# Manipulator_loads.net
KiCad netlist of a schematic drawn in EAGLE
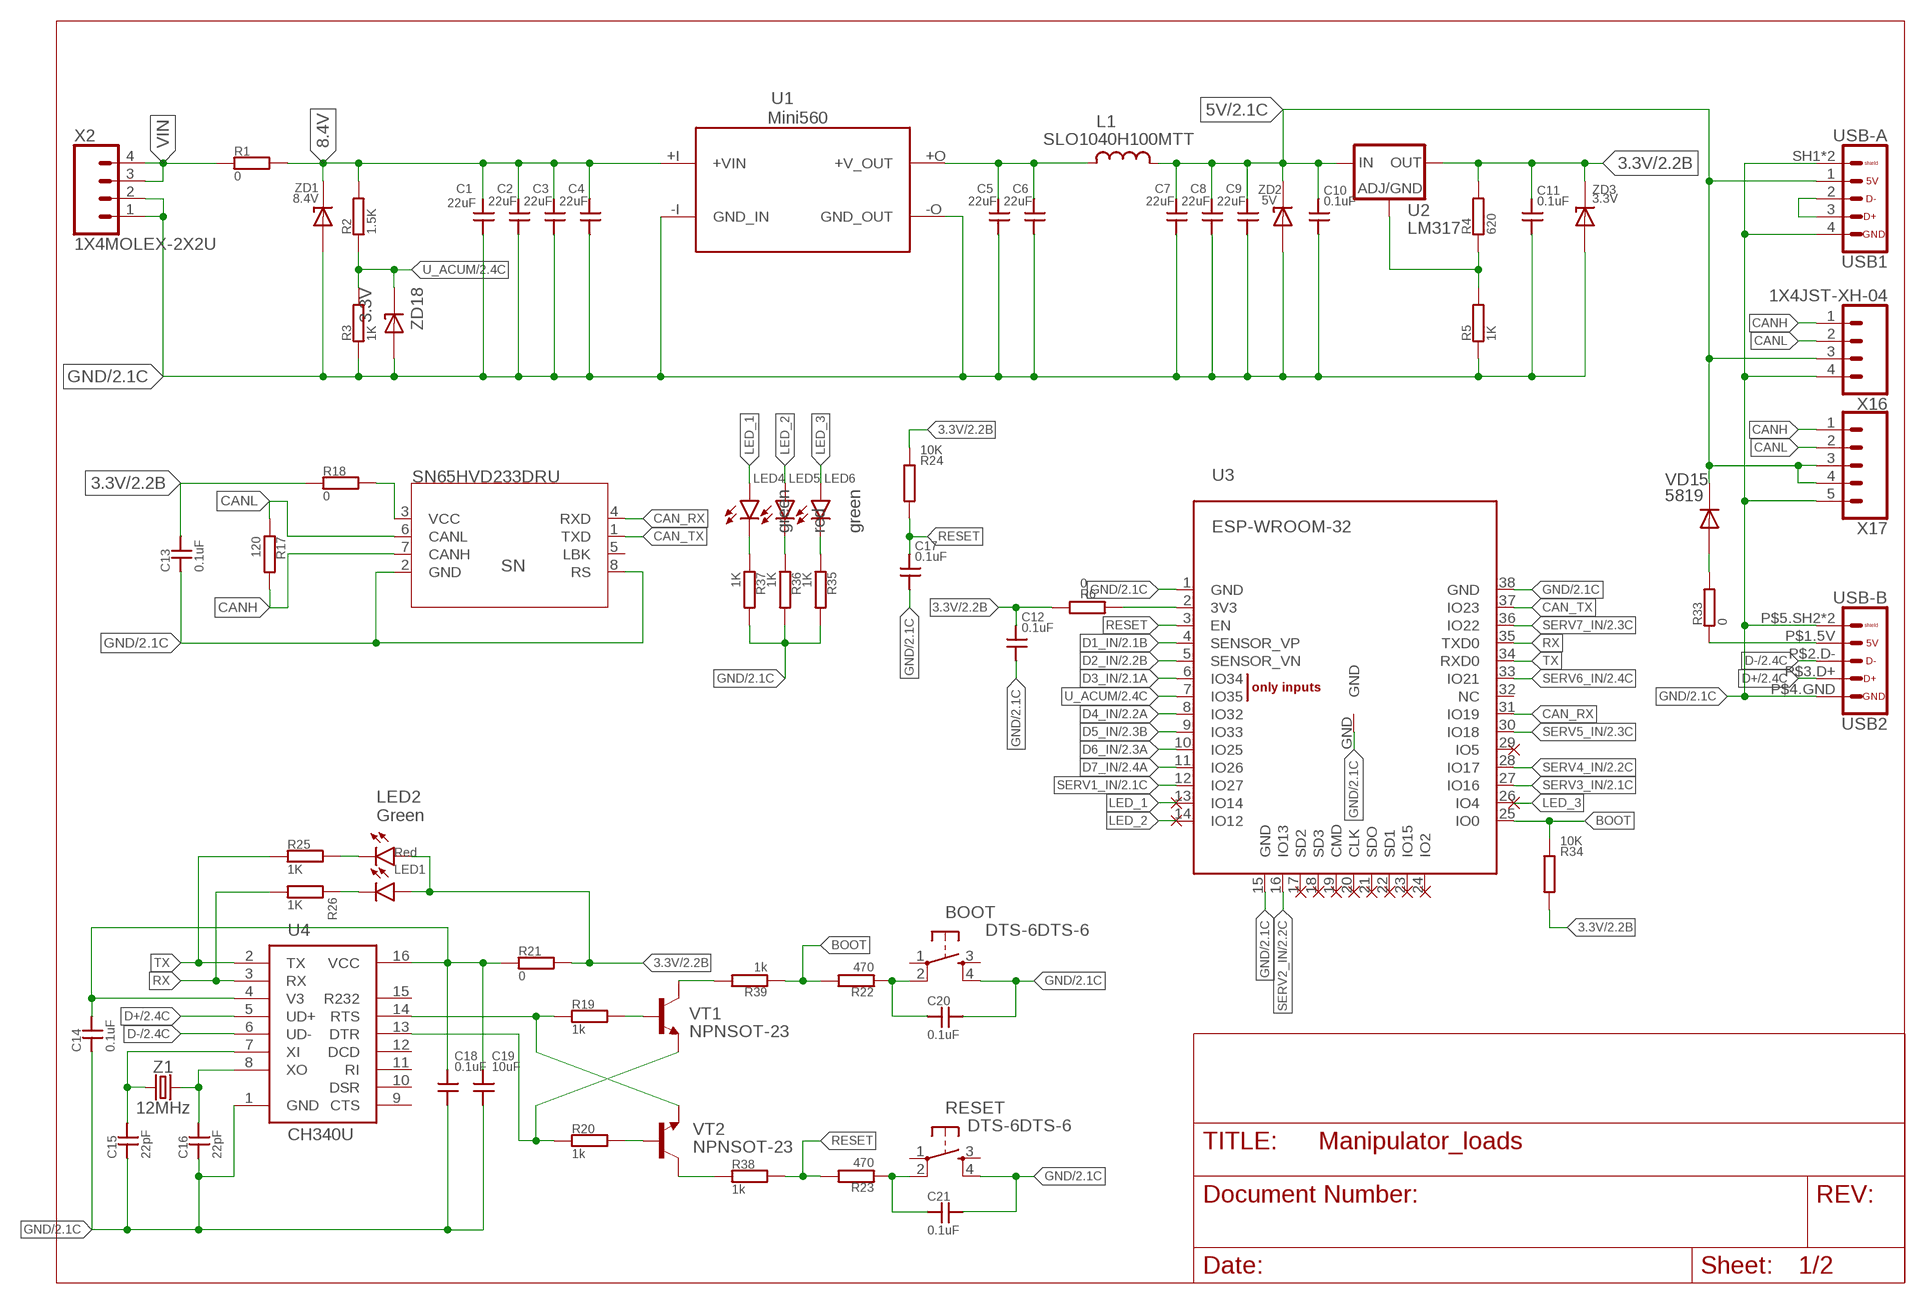
[diagram p0: schematic, sheet 1]
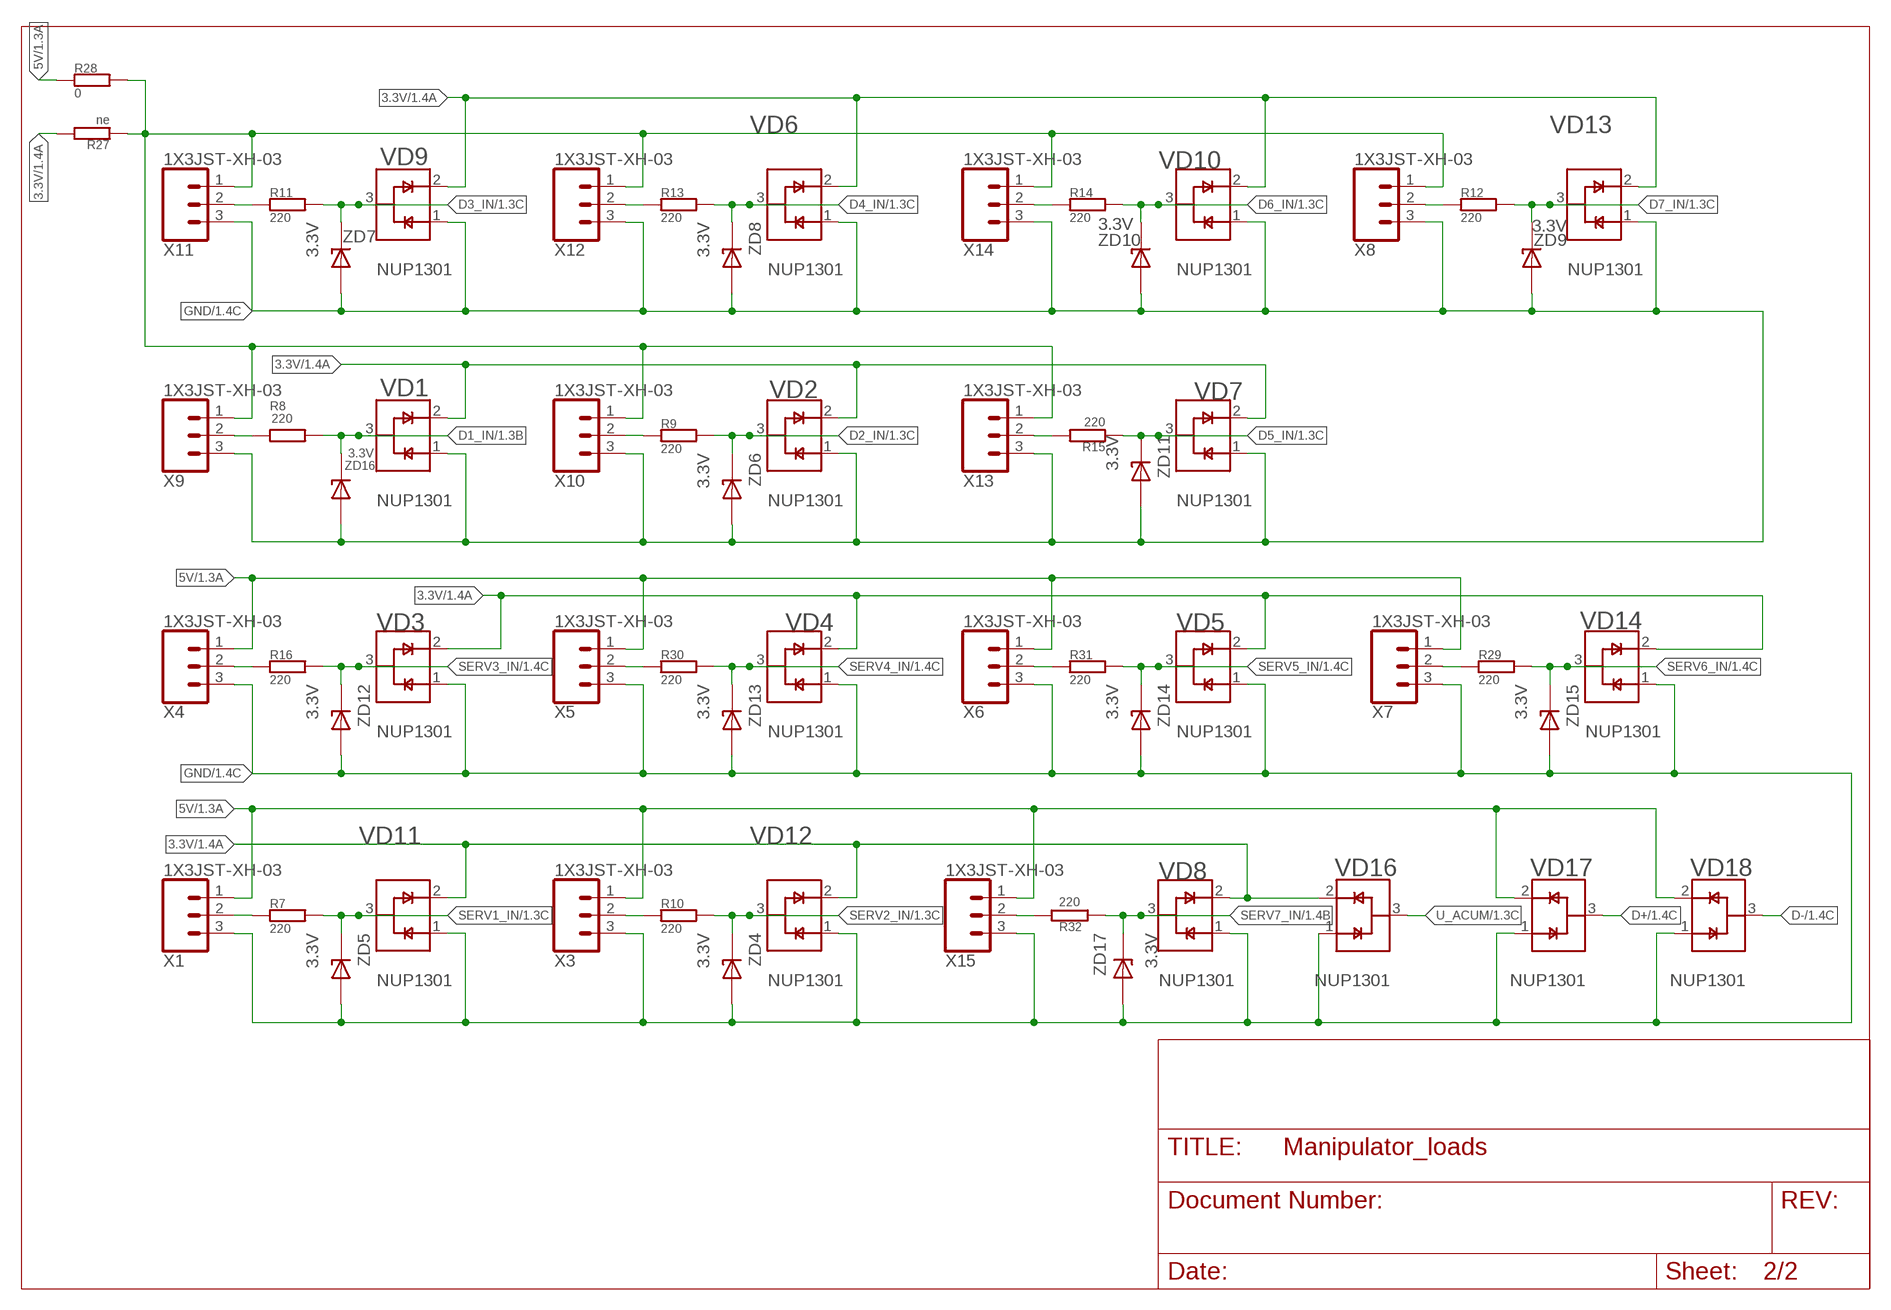
[diagram p1: schematic, sheet 2]

(export (version "E")
  (design (tool "Eeschema 10.0.6"))
  (components
    (comp (ref "BOOT")
      (value "DTS-6DTS-6")
      (footprint "eagle-import:DTS-6")
      (libsource (lib "eagle-import") (part "DTS-6DTS-6"))
    )
    (comp (ref "C1")
      (value "22uF")
      (footprint "eagle-import:1206")
      (libsource (lib "eagle-import") (part "C1206"))
    )
    (comp (ref "C2")
      (value "22uF")
      (footprint "eagle-import:1206")
      (libsource (lib "eagle-import") (part "C1206"))
    )
    (comp (ref "C3")
      (value "22uF")
      (footprint "eagle-import:1206")
      (libsource (lib "eagle-import") (part "C1206"))
    )
    (comp (ref "C4")
      (value "22uF")
      (footprint "eagle-import:1206")
      (libsource (lib "eagle-import") (part "C1206"))
    )
    (comp (ref "C5")
      (value "22uF")
      (footprint "eagle-import:1206")
      (libsource (lib "eagle-import") (part "C1206"))
    )
    (comp (ref "C6")
      (value "22uF")
      (footprint "eagle-import:1206")
      (libsource (lib "eagle-import") (part "C1206"))
    )
    (comp (ref "C7")
      (value "22uF")
      (footprint "eagle-import:1206")
      (libsource (lib "eagle-import") (part "C1206"))
    )
    (comp (ref "C8")
      (value "22uF")
      (footprint "eagle-import:1206")
      (libsource (lib "eagle-import") (part "C1206"))
    )
    (comp (ref "C9")
      (value "22uF")
      (footprint "eagle-import:1206")
      (libsource (lib "eagle-import") (part "C1206"))
    )
    (comp (ref "C10")
      (value "0.1uF")
      (footprint "eagle-import:0603")
      (libsource (lib "eagle-import") (part "C0603"))
    )
    (comp (ref "C11")
      (value "0.1uF")
      (footprint "eagle-import:0603")
      (libsource (lib "eagle-import") (part "C0603"))
    )
    (comp (ref "C12")
      (value "0.1uF")
      (footprint "eagle-import:0603")
      (libsource (lib "eagle-import") (part "C0603"))
    )
    (comp (ref "C13")
      (value "0.1uF")
      (footprint "eagle-import:0603")
      (libsource (lib "eagle-import") (part "C0603"))
    )
    (comp (ref "C14")
      (value "0.1uF")
      (footprint "eagle-import:0603")
      (libsource (lib "eagle-import") (part "C0603"))
    )
    (comp (ref "C15")
      (value "22pF")
      (footprint "eagle-import:0603")
      (libsource (lib "eagle-import") (part "C0603"))
    )
    (comp (ref "C16")
      (value "22pF")
      (footprint "eagle-import:0603")
      (libsource (lib "eagle-import") (part "C0603"))
    )
    (comp (ref "C17")
      (value "0.1uF")
      (footprint "eagle-import:0603")
      (libsource (lib "eagle-import") (part "C0603"))
    )
    (comp (ref "C18")
      (value "0.1uF")
      (footprint "eagle-import:0603")
      (libsource (lib "eagle-import") (part "C0603"))
    )
    (comp (ref "C19")
      (value "10uF")
      (footprint "eagle-import:0603")
      (libsource (lib "eagle-import") (part "C0603"))
    )
    (comp (ref "C20")
      (value "0.1uF")
      (footprint "eagle-import:0603")
      (libsource (lib "eagle-import") (part "C0603"))
    )
    (comp (ref "C21")
      (value "0.1uF")
      (footprint "eagle-import:0603")
      (libsource (lib "eagle-import") (part "C0603"))
    )
    (comp (ref "L1")
      (value "SLO1040H100MTT")
      (footprint "eagle-import:108100X400")
      (libsource (lib "eagle-import") (part "INDUCTOR108100X400"))
    )
    (comp (ref "LED1")
      (value "Red")
      (footprint "eagle-import:1608")
      (libsource (lib "eagle-import") (part "LED1608"))
    )
    (comp (ref "LED2")
      (value "Green")
      (footprint "eagle-import:1608")
      (libsource (lib "eagle-import") (part "LED1608"))
    )
    (comp (ref "LED4")
      (value "green")
      (footprint "eagle-import:1608")
      (libsource (lib "eagle-import") (part "LED1608"))
    )
    (comp (ref "LED5")
      (value "red")
      (footprint "eagle-import:1608")
      (libsource (lib "eagle-import") (part "LED1608"))
    )
    (comp (ref "LED6")
      (value "green")
      (footprint "eagle-import:1608")
      (libsource (lib "eagle-import") (part "LED1608"))
    )
    (comp (ref "R1")
      (value "0")
      (footprint "eagle-import:2512")
      (libsource (lib "eagle-import") (part "R2512"))
    )
    (comp (ref "R2")
      (value "1.5K")
      (footprint "eagle-import:0603")
      (libsource (lib "eagle-import") (part "R0603"))
    )
    (comp (ref "R3")
      (value "1K")
      (footprint "eagle-import:0603")
      (libsource (lib "eagle-import") (part "R0603"))
    )
    (comp (ref "R4")
      (value "620")
      (footprint "eagle-import:0603")
      (libsource (lib "eagle-import") (part "R0603"))
    )
    (comp (ref "R5")
      (value "1K")
      (footprint "eagle-import:0603")
      (libsource (lib "eagle-import") (part "R0603"))
    )
    (comp (ref "R6")
      (value "0")
      (footprint "eagle-import:0603")
      (libsource (lib "eagle-import") (part "R0603"))
    )
    (comp (ref "R17")
      (value "120")
      (footprint "eagle-import:0603")
      (libsource (lib "eagle-import") (part "R0603"))
    )
    (comp (ref "R18")
      (value "0")
      (footprint "eagle-import:0603")
      (libsource (lib "eagle-import") (part "R0603"))
    )
    (comp (ref "R19")
      (value "1k")
      (footprint "eagle-import:0603")
      (libsource (lib "eagle-import") (part "R0603"))
    )
    (comp (ref "R20")
      (value "1k")
      (footprint "eagle-import:0603")
      (libsource (lib "eagle-import") (part "R0603"))
    )
    (comp (ref "R21")
      (value "0")
      (footprint "eagle-import:0603")
      (libsource (lib "eagle-import") (part "R0603"))
    )
    (comp (ref "R22")
      (value "470")
      (footprint "eagle-import:0603")
      (libsource (lib "eagle-import") (part "R0603"))
    )
    (comp (ref "R23")
      (value "470")
      (footprint "eagle-import:0603")
      (libsource (lib "eagle-import") (part "R0603"))
    )
    (comp (ref "R24")
      (value "10K")
      (footprint "eagle-import:0603")
      (libsource (lib "eagle-import") (part "R0603"))
    )
    (comp (ref "R25")
      (value "1K")
      (footprint "eagle-import:0603")
      (libsource (lib "eagle-import") (part "R0603"))
    )
    (comp (ref "R26")
      (value "1K")
      (footprint "eagle-import:0603")
      (libsource (lib "eagle-import") (part "R0603"))
    )
    (comp (ref "R33")
      (value "0")
      (footprint "eagle-import:0603")
      (libsource (lib "eagle-import") (part "R0603"))
    )
    (comp (ref "R34")
      (value "10K")
      (footprint "eagle-import:0603")
      (libsource (lib "eagle-import") (part "R0603"))
    )
    (comp (ref "R35")
      (value "1K")
      (footprint "eagle-import:0603")
      (libsource (lib "eagle-import") (part "R0603"))
    )
    (comp (ref "R36")
      (value "1K")
      (footprint "eagle-import:0603")
      (libsource (lib "eagle-import") (part "R0603"))
    )
    (comp (ref "R37")
      (value "1K")
      (footprint "eagle-import:0603")
      (libsource (lib "eagle-import") (part "R0603"))
    )
    (comp (ref "R38")
      (value "1k")
      (footprint "eagle-import:0603")
      (libsource (lib "eagle-import") (part "R0603"))
    )
    (comp (ref "R39")
      (value "1k")
      (footprint "eagle-import:0603")
      (libsource (lib "eagle-import") (part "R0603"))
    )
    (comp (ref "RESET")
      (value "DTS-6DTS-6")
      (footprint "eagle-import:DTS-6")
      (libsource (lib "eagle-import") (part "DTS-6DTS-6"))
    )
    (comp (ref "SN")
      (value "SN65HVD233DRU")
      (footprint "eagle-import:SOIC-8")
      (libsource (lib "eagle-import") (part "SN65HVD233DRU"))
    )
    (comp (ref "U1")
      (value "Mini560")
      (footprint "eagle-import:MINI560_OTB")
      (libsource (lib "eagle-import") (part "MINI560"))
    )
    (comp (ref "U2")
      (value "LM317")
      (footprint "eagle-import:D-PAK")
      (libsource (lib "eagle-import") (part "LM317"))
    )
    (comp (ref "U3")
      (value "ESP-WROOM-32")
      (footprint "eagle-import:ESP-WROOM-32")
      (libsource (lib "eagle-import") (part "ESP-WROOM-32"))
    )
    (comp (ref "U4")
      (value "CH340U")
      (footprint "eagle-import:SOIC-16")
      (libsource (lib "eagle-import") (part "CH340U"))
    )
    (comp (ref "USB1")
      (value "USB-A")
      (footprint "eagle-import:A-VERTICAL")
      (libsource (lib "eagle-import") (part "USB-A"))
    )
    (comp (ref "USB2")
      (value "USB-B")
      (footprint "eagle-import:B-VERTICAL")
      (libsource (lib "eagle-import") (part "USB-B"))
    )
    (comp (ref "VD15")
      (value "5819")
      (footprint "eagle-import:SOD123")
      (libsource (lib "eagle-import") (part "DIODESOD-123"))
    )
    (comp (ref "VT1")
      (value "NPNSOT-23")
      (footprint "eagle-import:SOT-23")
      (libsource (lib "eagle-import") (part "NPNSOT-23"))
    )
    (comp (ref "VT2")
      (value "NPNSOT-23")
      (footprint "eagle-import:SOT-23")
      (libsource (lib "eagle-import") (part "NPNSOT-23"))
    )
    (comp (ref "X2")
      (value "1X4MOLEX-2X2U")
      (footprint "eagle-import:MOLEX-2X2U")
      (libsource (lib "eagle-import") (part "1X4MOLEX-2X2U"))
    )
    (comp (ref "X16")
      (value "1X4JST-XH-04")
      (footprint "eagle-import:JST-XH-04")
      (libsource (lib "eagle-import") (part "1X4JST-XH-04"))
    )
    (comp (ref "X17")
      (value "1X5JST-XH-05")
      (footprint "eagle-import:JST-XH-05")
      (libsource (lib "eagle-import") (part "1X5JST-XH-05"))
    )
    (comp (ref "Z1")
      (value "12MHz")
      (footprint "eagle-import:CRYSTAL-SMD-3.2X2.5MM")
      (libsource (lib "eagle-import") (part "CRYSTAL4FOOT"))
    )
    (comp (ref "ZD1")
      (value "8.4V")
      (footprint "eagle-import:SMB")
      (libsource (lib "eagle-import") (part "ZENER-DIODESSMB"))
    )
    (comp (ref "ZD2")
      (value "5V")
      (footprint "eagle-import:SMB")
      (libsource (lib "eagle-import") (part "ZENER-DIODESSMB"))
    )
    (comp (ref "ZD3")
      (value "3.3V")
      (footprint "eagle-import:MINIMELF")
      (libsource (lib "eagle-import") (part "ZENER-DIODESMINIMELF"))
    )
    (comp (ref "ZD18")
      (value "3.3V")
      (footprint "eagle-import:MINIMELF")
      (libsource (lib "eagle-import") (part "ZENER-DIODESMINIMELF"))
    )
    (comp (ref "R7")
      (value "220")
      (footprint "eagle-import:0603")
      (libsource (lib "eagle-import") (part "R0603"))
    )
    (comp (ref "R8")
      (value "220")
      (footprint "eagle-import:0603")
      (libsource (lib "eagle-import") (part "R0603"))
    )
    (comp (ref "R9")
      (value "220")
      (footprint "eagle-import:0603")
      (libsource (lib "eagle-import") (part "R0603"))
    )
    (comp (ref "R10")
      (value "220")
      (footprint "eagle-import:0603")
      (libsource (lib "eagle-import") (part "R0603"))
    )
    (comp (ref "R11")
      (value "220")
      (footprint "eagle-import:0603")
      (libsource (lib "eagle-import") (part "R0603"))
    )
    (comp (ref "R12")
      (value "220")
      (footprint "eagle-import:0603")
      (libsource (lib "eagle-import") (part "R0603"))
    )
    (comp (ref "R13")
      (value "220")
      (footprint "eagle-import:0603")
      (libsource (lib "eagle-import") (part "R0603"))
    )
    (comp (ref "R14")
      (value "220")
      (footprint "eagle-import:0603")
      (libsource (lib "eagle-import") (part "R0603"))
    )
    (comp (ref "R15")
      (value "220")
      (footprint "eagle-import:0603")
      (libsource (lib "eagle-import") (part "R0603"))
    )
    (comp (ref "R16")
      (value "220")
      (footprint "eagle-import:0603")
      (libsource (lib "eagle-import") (part "R0603"))
    )
    (comp (ref "R27")
      (value "ne")
      (footprint "eagle-import:0603")
      (libsource (lib "eagle-import") (part "R0603"))
    )
    (comp (ref "R28")
      (value "0")
      (footprint "eagle-import:0603")
      (libsource (lib "eagle-import") (part "R0603"))
    )
    (comp (ref "R29")
      (value "220")
      (footprint "eagle-import:0603")
      (libsource (lib "eagle-import") (part "R0603"))
    )
    (comp (ref "R30")
      (value "220")
      (footprint "eagle-import:0603")
      (libsource (lib "eagle-import") (part "R0603"))
    )
    (comp (ref "R31")
      (value "220")
      (footprint "eagle-import:0603")
      (libsource (lib "eagle-import") (part "R0603"))
    )
    (comp (ref "R32")
      (value "220")
      (footprint "eagle-import:0603")
      (libsource (lib "eagle-import") (part "R0603"))
    )
    (comp (ref "VD1")
      (value "BAV99.215")
      (footprint "eagle-import:SOT23")
      (libsource (lib "eagle-import") (part "ESD_PROTECTIONSOT123"))
    )
    (comp (ref "VD2")
      (value "BAV99.215")
      (footprint "eagle-import:SOT23")
      (libsource (lib "eagle-import") (part "ESD_PROTECTIONSOT123"))
    )
    (comp (ref "VD3")
      (value "BAV99.215")
      (footprint "eagle-import:SOT23")
      (libsource (lib "eagle-import") (part "ESD_PROTECTIONSOT123"))
    )
    (comp (ref "VD4")
      (value "BAV99.215")
      (footprint "eagle-import:SOT23")
      (libsource (lib "eagle-import") (part "ESD_PROTECTIONSOT123"))
    )
    (comp (ref "VD5")
      (value "BAV99.215")
      (footprint "eagle-import:SOT23")
      (libsource (lib "eagle-import") (part "ESD_PROTECTIONSOT123"))
    )
    (comp (ref "VD6")
      (value "BAV99")
      (footprint "eagle-import:SOT23")
      (libsource (lib "eagle-import") (part "ESD_PROTECTIONSOT123"))
    )
    (comp (ref "VD7")
      (value "BAV99.215")
      (footprint "eagle-import:SOT23")
      (libsource (lib "eagle-import") (part "ESD_PROTECTIONSOT123"))
    )
    (comp (ref "VD8")
      (value "BAV99.215")
      (footprint "eagle-import:SOT23")
      (libsource (lib "eagle-import") (part "ESD_PROTECTIONSOT123"))
    )
    (comp (ref "VD9")
      (value "BAV99")
      (footprint "eagle-import:SOT23")
      (libsource (lib "eagle-import") (part "ESD_PROTECTIONSOT123"))
    )
    (comp (ref "VD10")
      (value "BAV99.215")
      (footprint "eagle-import:SOT23")
      (libsource (lib "eagle-import") (part "ESD_PROTECTIONSOT123"))
    )
    (comp (ref "VD11")
      (value "BAV99.215")
      (footprint "eagle-import:SOT23")
      (libsource (lib "eagle-import") (part "ESD_PROTECTIONSOT123"))
    )
    (comp (ref "VD12")
      (value "BAV99.215")
      (footprint "eagle-import:SOT23")
      (libsource (lib "eagle-import") (part "ESD_PROTECTIONSOT123"))
    )
    (comp (ref "VD13")
      (value "BAV99.215")
      (footprint "eagle-import:SOT23")
      (libsource (lib "eagle-import") (part "ESD_PROTECTIONSOT123"))
    )
    (comp (ref "VD14")
      (value "BAV99.215")
      (footprint "eagle-import:SOT23")
      (libsource (lib "eagle-import") (part "ESD_PROTECTIONSOT123"))
    )
    (comp (ref "VD16")
      (value "BAV99.215")
      (footprint "eagle-import:SOT23")
      (libsource (lib "eagle-import") (part "ESD_PROTECTIONSOT123"))
    )
    (comp (ref "VD17")
      (value "BAV99.215")
      (footprint "eagle-import:SOT23")
      (libsource (lib "eagle-import") (part "ESD_PROTECTIONSOT123"))
    )
    (comp (ref "VD18")
      (value "BAV99.215")
      (footprint "eagle-import:SOT23")
      (libsource (lib "eagle-import") (part "ESD_PROTECTIONSOT123"))
    )
    (comp (ref "X1")
      (value "1X3JST-XH-03")
      (footprint "eagle-import:JST-XH-03")
      (libsource (lib "eagle-import") (part "1X3JST-XH-03"))
    )
    (comp (ref "X3")
      (value "1X3JST-XH-03")
      (footprint "eagle-import:JST-XH-03")
      (libsource (lib "eagle-import") (part "1X3JST-XH-03"))
    )
    (comp (ref "X4")
      (value "1X3JST-XH-03")
      (footprint "eagle-import:JST-XH-03")
      (libsource (lib "eagle-import") (part "1X3JST-XH-03"))
    )
    (comp (ref "X5")
      (value "1X3JST-XH-03")
      (footprint "eagle-import:JST-XH-03")
      (libsource (lib "eagle-import") (part "1X3JST-XH-03"))
    )
    (comp (ref "X6")
      (value "1X3JST-XH-03")
      (footprint "eagle-import:JST-XH-03")
      (libsource (lib "eagle-import") (part "1X3JST-XH-03"))
    )
    (comp (ref "X7")
      (value "1X3JST-XH-03")
      (footprint "eagle-import:JST-XH-03")
      (libsource (lib "eagle-import") (part "1X3JST-XH-03"))
    )
    (comp (ref "X8")
      (value "1X3JST-XH-03")
      (footprint "eagle-import:JST-XH-03")
      (libsource (lib "eagle-import") (part "1X3JST-XH-03"))
    )
    (comp (ref "X9")
      (value "1X3JST-XH-03")
      (footprint "eagle-import:JST-XH-03")
      (libsource (lib "eagle-import") (part "1X3JST-XH-03"))
    )
    (comp (ref "X10")
      (value "1X3JST-XH-03")
      (footprint "eagle-import:JST-XH-03")
      (libsource (lib "eagle-import") (part "1X3JST-XH-03"))
    )
    (comp (ref "X11")
      (value "1X3JST-XH-03")
      (footprint "eagle-import:JST-XH-03")
      (libsource (lib "eagle-import") (part "1X3JST-XH-03"))
    )
    (comp (ref "X12")
      (value "1X3JST-XH-03")
      (footprint "eagle-import:JST-XH-03")
      (libsource (lib "eagle-import") (part "1X3JST-XH-03"))
    )
    (comp (ref "X13")
      (value "1X3JST-XH-03")
      (footprint "eagle-import:JST-XH-03")
      (libsource (lib "eagle-import") (part "1X3JST-XH-03"))
    )
    (comp (ref "X14")
      (value "1X3JST-XH-03")
      (footprint "eagle-import:JST-XH-03")
      (libsource (lib "eagle-import") (part "1X3JST-XH-03"))
    )
    (comp (ref "X15")
      (value "1X3JST-XH-03")
      (footprint "eagle-import:JST-XH-03")
      (libsource (lib "eagle-import") (part "1X3JST-XH-03"))
    )
    (comp (ref "ZD4")
      (value "3.3V")
      (footprint "eagle-import:MINIMELF")
      (libsource (lib "eagle-import") (part "ZENER-DIODESMINIMELF"))
    )
    (comp (ref "ZD5")
      (value "3.3V")
      (footprint "eagle-import:MINIMELF")
      (libsource (lib "eagle-import") (part "ZENER-DIODESMINIMELF"))
    )
    (comp (ref "ZD6")
      (value "3.3V")
      (footprint "eagle-import:MINIMELF")
      (libsource (lib "eagle-import") (part "ZENER-DIODESMINIMELF"))
    )
    (comp (ref "ZD7")
      (value "3.3V")
      (footprint "eagle-import:MINIMELF")
      (libsource (lib "eagle-import") (part "ZENER-DIODESMINIMELF"))
    )
    (comp (ref "ZD8")
      (value "3.3V")
      (footprint "eagle-import:MINIMELF")
      (libsource (lib "eagle-import") (part "ZENER-DIODESMINIMELF"))
    )
    (comp (ref "ZD9")
      (value "3.3V")
      (footprint "eagle-import:MINIMELF")
      (libsource (lib "eagle-import") (part "ZENER-DIODESMINIMELF"))
    )
    (comp (ref "ZD10")
      (value "3.3V")
      (footprint "eagle-import:MINIMELF")
      (libsource (lib "eagle-import") (part "ZENER-DIODESMINIMELF"))
    )
    (comp (ref "ZD11")
      (value "3.3V")
      (footprint "eagle-import:MINIMELF")
      (libsource (lib "eagle-import") (part "ZENER-DIODESMINIMELF"))
    )
    (comp (ref "ZD12")
      (value "3.3V")
      (footprint "eagle-import:MINIMELF")
      (libsource (lib "eagle-import") (part "ZENER-DIODESMINIMELF"))
    )
    (comp (ref "ZD13")
      (value "3.3V")
      (footprint "eagle-import:MINIMELF")
      (libsource (lib "eagle-import") (part "ZENER-DIODESMINIMELF"))
    )
    (comp (ref "ZD14")
      (value "3.3V")
      (footprint "eagle-import:MINIMELF")
      (libsource (lib "eagle-import") (part "ZENER-DIODESMINIMELF"))
    )
    (comp (ref "ZD15")
      (value "3.3V")
      (footprint "eagle-import:MINIMELF")
      (libsource (lib "eagle-import") (part "ZENER-DIODESMINIMELF"))
    )
    (comp (ref "ZD16")
      (value "3.3V")
      (footprint "eagle-import:MINIMELF")
      (libsource (lib "eagle-import") (part "ZENER-DIODESMINIMELF"))
    )
    (comp (ref "ZD17")
      (value "3.3V")
      (footprint "eagle-import:MINIMELF")
      (libsource (lib "eagle-import") (part "ZENER-DIODESMINIMELF"))
    )
  )
  (nets
    (net (code "1") (name "3.3V") (class "Default")
      (node (ref "C11") (pin "P$2") (pinfunction "P$2_P$2") (pintype "bidirectional"))
      (node (ref "C12") (pin "P$2") (pinfunction "P$2_P$2") (pintype "bidirectional"))
      (node (ref "C13") (pin "P$2") (pinfunction "P$2_P$2") (pintype "bidirectional"))
      (node (ref "LED1") (pin "P$2") (pinfunction "A_P$2") (pintype "passive"))
      (node (ref "LED2") (pin "P$2") (pinfunction "A_P$2") (pintype "passive"))
      (node (ref "R18") (pin "P$1") (pinfunction "P$1_P$1") (pintype "bidirectional"))
      (node (ref "R21") (pin "P$2") (pinfunction "P$2_P$2") (pintype "bidirectional"))
      (node (ref "R24") (pin "P$1") (pinfunction "P$1_P$1") (pintype "bidirectional"))
      (node (ref "R27") (pin "P$2") (pinfunction "P$2_P$2") (pintype "bidirectional"))
      (node (ref "R34") (pin "P$2") (pinfunction "P$2_P$2") (pintype "bidirectional"))
      (node (ref "R4") (pin "P$2") (pinfunction "P$2_P$2") (pintype "bidirectional"))
      (node (ref "R6") (pin "P$2") (pinfunction "P$2_P$2") (pintype "bidirectional"))
      (node (ref "U2") (pin "4") (pinfunction "OUT_4") (pintype "passive"))
      (node (ref "VD1") (pin "2") (pinfunction "VCC_2") (pintype "bidirectional"))
      (node (ref "VD10") (pin "2") (pinfunction "VCC_2") (pintype "bidirectional"))
      (node (ref "VD11") (pin "2") (pinfunction "VCC_2") (pintype "bidirectional"))
      (node (ref "VD12") (pin "2") (pinfunction "VCC_2") (pintype "bidirectional"))
      (node (ref "VD13") (pin "2") (pinfunction "VCC_2") (pintype "bidirectional"))
      (node (ref "VD14") (pin "2") (pinfunction "VCC_2") (pintype "bidirectional"))
      (node (ref "VD16") (pin "2") (pinfunction "VCC_2") (pintype "bidirectional"))
      (node (ref "VD2") (pin "2") (pinfunction "VCC_2") (pintype "bidirectional"))
      (node (ref "VD3") (pin "2") (pinfunction "VCC_2") (pintype "bidirectional"))
      (node (ref "VD4") (pin "2") (pinfunction "VCC_2") (pintype "bidirectional"))
      (node (ref "VD5") (pin "2") (pinfunction "VCC_2") (pintype "bidirectional"))
      (node (ref "VD6") (pin "2") (pinfunction "VCC_2") (pintype "bidirectional"))
      (node (ref "VD7") (pin "2") (pinfunction "VCC_2") (pintype "bidirectional"))
      (node (ref "VD8") (pin "2") (pinfunction "VCC_2") (pintype "bidirectional"))
      (node (ref "VD9") (pin "2") (pinfunction "VCC_2") (pintype "bidirectional"))
      (node (ref "ZD3") (pin "C") (pinfunction "C_C") (pintype "passive"))
    )
    (net (code "2") (name "5V") (class "Default")
      (node (ref "C10") (pin "P$2") (pinfunction "P$2_P$2") (pintype "bidirectional"))
      (node (ref "C7") (pin "P$2") (pinfunction "P$2_P$2") (pintype "bidirectional"))
      (node (ref "C8") (pin "P$2") (pinfunction "P$2_P$2") (pintype "bidirectional"))
      (node (ref "C9") (pin "P$2") (pinfunction "P$2_P$2") (pintype "bidirectional"))
      (node (ref "L1") (pin "2") (pinfunction "2_2") (pintype "passive"))
      (node (ref "R28") (pin "P$1") (pinfunction "P$1_P$1") (pintype "bidirectional"))
      (node (ref "U2") (pin "3") (pinfunction "IN_3") (pintype "input"))
      (node (ref "USB1") (pin "1") (pinfunction "1_1") (pintype "passive"))
      (node (ref "VD15") (pin "C") (pinfunction "C_C") (pintype "passive"))
      (node (ref "VD17") (pin "2") (pinfunction "VCC_2") (pintype "bidirectional"))
      (node (ref "VD18") (pin "2") (pinfunction "VCC_2") (pintype "bidirectional"))
      (node (ref "X1") (pin "1") (pinfunction "1_1") (pintype "passive"))
      (node (ref "X15") (pin "1") (pinfunction "1_1") (pintype "passive"))
      (node (ref "X16") (pin "3") (pinfunction "3_3") (pintype "passive"))
      (node (ref "X17") (pin "3") (pinfunction "3_3") (pintype "passive"))
      (node (ref "X17") (pin "4") (pinfunction "4_4") (pintype "passive"))
      (node (ref "X3") (pin "1") (pinfunction "1_1") (pintype "passive"))
      (node (ref "X4") (pin "1") (pinfunction "1_1") (pintype "passive"))
      (node (ref "X5") (pin "1") (pinfunction "1_1") (pintype "passive"))
      (node (ref "X6") (pin "1") (pinfunction "1_1") (pintype "passive"))
      (node (ref "X7") (pin "1") (pinfunction "1_1") (pintype "passive"))
      (node (ref "ZD2") (pin "C") (pinfunction "C_C") (pintype "passive"))
    )
    (net (code "3") (name "8.4V") (class "Default")
      (node (ref "C1") (pin "P$2") (pinfunction "P$2_P$2") (pintype "bidirectional"))
      (node (ref "C2") (pin "P$2") (pinfunction "P$2_P$2") (pintype "bidirectional"))
      (node (ref "C3") (pin "P$2") (pinfunction "P$2_P$2") (pintype "bidirectional"))
      (node (ref "C4") (pin "P$2") (pinfunction "P$2_P$2") (pintype "bidirectional"))
      (node (ref "R1") (pin "2") (pinfunction "P$2_2") (pintype "bidirectional"))
      (node (ref "R2") (pin "P$2") (pinfunction "P$2_P$2") (pintype "bidirectional"))
      (node (ref "U1") (pin "+I") (pinfunction "+VIN_+I") (pintype "bidirectional"))
      (node (ref "ZD1") (pin "C") (pinfunction "C_C") (pintype "passive"))
    )
    (net (code "4") (name "BOOT") (class "Default")
      (node (ref "R22") (pin "P$2") (pinfunction "P$2_P$2") (pintype "bidirectional"))
      (node (ref "R34") (pin "P$1") (pinfunction "P$1_P$1") (pintype "bidirectional"))
      (node (ref "R39") (pin "P$1") (pinfunction "P$1_P$1") (pintype "bidirectional"))
      (node (ref "U3") (pin "25") (pinfunction "IO0_25") (pintype "bidirectional"))
    )
    (net (code "5") (name "CANH") (class "Default")
      (node (ref "R17") (pin "P$2") (pinfunction "P$2_P$2") (pintype "bidirectional"))
      (node (ref "SN") (pin "7") (pinfunction "CANH_7") (pintype "bidirectional"))
      (node (ref "X16") (pin "1") (pinfunction "1_1") (pintype "passive"))
      (node (ref "X17") (pin "1") (pinfunction "1_1") (pintype "passive"))
    )
    (net (code "6") (name "CANL") (class "Default")
      (node (ref "R17") (pin "P$1") (pinfunction "P$1_P$1") (pintype "bidirectional"))
      (node (ref "SN") (pin "6") (pinfunction "CANL_6") (pintype "bidirectional"))
      (node (ref "X16") (pin "2") (pinfunction "2_2") (pintype "passive"))
      (node (ref "X17") (pin "2") (pinfunction "2_2") (pintype "passive"))
    )
    (net (code "7") (name "CAN_RX") (class "Default")
      (node (ref "SN") (pin "4") (pinfunction "RXD_4") (pintype "bidirectional"))
      (node (ref "U3") (pin "31") (pinfunction "IO19_31") (pintype "bidirectional"))
    )
    (net (code "8") (name "CAN_TX") (class "Default")
      (node (ref "SN") (pin "1") (pinfunction "TXD_1") (pintype "bidirectional"))
      (node (ref "U3") (pin "37") (pinfunction "IO23_37") (pintype "bidirectional"))
    )
    (net (code "9") (name "D+") (class "Default")
      (node (ref "U4") (pin "5") (pinfunction "UD+_5") (pintype "bidirectional"))
      (node (ref "USB2") (pin "P$3.D+") (pinfunction "3_P$3.D+") (pintype "passive"))
      (node (ref "VD17") (pin "3") (pinfunction "I/O_3") (pintype "bidirectional"))
    )
    (net (code "10") (name "D-") (class "Default")
      (node (ref "U4") (pin "6") (pinfunction "UD-_6") (pintype "bidirectional"))
      (node (ref "USB2") (pin "P$2.D-") (pinfunction "2_P$2.D-") (pintype "passive"))
      (node (ref "VD18") (pin "3") (pinfunction "I/O_3") (pintype "bidirectional"))
    )
    (net (code "11") (name "D1_IN") (class "Default")
      (node (ref "R8") (pin "P$2") (pinfunction "P$2_P$2") (pintype "bidirectional"))
      (node (ref "U3") (pin "4") (pinfunction "SENSOR_VP_4") (pintype "input"))
      (node (ref "VD1") (pin "3") (pinfunction "I/O_3") (pintype "bidirectional"))
      (node (ref "ZD16") (pin "C") (pinfunction "C_C") (pintype "passive"))
    )
    (net (code "12") (name "D2_IN") (class "Default")
      (node (ref "R9") (pin "P$2") (pinfunction "P$2_P$2") (pintype "bidirectional"))
      (node (ref "U3") (pin "5") (pinfunction "SENSOR_VN_5") (pintype "input"))
      (node (ref "VD2") (pin "3") (pinfunction "I/O_3") (pintype "bidirectional"))
      (node (ref "ZD6") (pin "C") (pinfunction "C_C") (pintype "passive"))
    )
    (net (code "13") (name "D3_IN") (class "Default")
      (node (ref "R11") (pin "P$2") (pinfunction "P$2_P$2") (pintype "bidirectional"))
      (node (ref "U3") (pin "6") (pinfunction "IO34_6") (pintype "input"))
      (node (ref "VD9") (pin "3") (pinfunction "I/O_3") (pintype "bidirectional"))
      (node (ref "ZD7") (pin "C") (pinfunction "C_C") (pintype "passive"))
    )
    (net (code "14") (name "D4_IN") (class "Default")
      (node (ref "R13") (pin "P$2") (pinfunction "P$2_P$2") (pintype "bidirectional"))
      (node (ref "U3") (pin "8") (pinfunction "IO32_8") (pintype "bidirectional"))
      (node (ref "VD6") (pin "3") (pinfunction "I/O_3") (pintype "bidirectional"))
      (node (ref "ZD8") (pin "C") (pinfunction "C_C") (pintype "passive"))
    )
    (net (code "15") (name "D5_IN") (class "Default")
      (node (ref "R15") (pin "P$1") (pinfunction "P$1_P$1") (pintype "bidirectional"))
      (node (ref "U3") (pin "9") (pinfunction "IO33_9") (pintype "bidirectional"))
      (node (ref "VD7") (pin "3") (pinfunction "I/O_3") (pintype "bidirectional"))
      (node (ref "ZD11") (pin "C") (pinfunction "C_C") (pintype "passive"))
    )
    (net (code "16") (name "D6_IN") (class "Default")
      (node (ref "R14") (pin "P$2") (pinfunction "P$2_P$2") (pintype "bidirectional"))
      (node (ref "U3") (pin "10") (pinfunction "IO25_10") (pintype "bidirectional"))
      (node (ref "VD10") (pin "3") (pinfunction "I/O_3") (pintype "bidirectional"))
      (node (ref "ZD10") (pin "C") (pinfunction "C_C") (pintype "passive"))
    )
    (net (code "17") (name "D7_IN") (class "Default")
      (node (ref "R12") (pin "P$2") (pinfunction "P$2_P$2") (pintype "bidirectional"))
      (node (ref "U3") (pin "11") (pinfunction "IO26_11") (pintype "bidirectional"))
      (node (ref "VD13") (pin "3") (pinfunction "I/O_3") (pintype "bidirectional"))
      (node (ref "ZD9") (pin "C") (pinfunction "C_C") (pintype "passive"))
    )
    (net (code "18") (name "GND") (class "Default")
      (node (ref "BOOT") (pin "4") (pinfunction "4_4") (pintype "passive"))
      (node (ref "C1") (pin "P$1") (pinfunction "P$1_P$1") (pintype "bidirectional"))
      (node (ref "C10") (pin "P$1") (pinfunction "P$1_P$1") (pintype "bidirectional"))
      (node (ref "C11") (pin "P$1") (pinfunction "P$1_P$1") (pintype "bidirectional"))
      (node (ref "C12") (pin "P$1") (pinfunction "P$1_P$1") (pintype "bidirectional"))
      (node (ref "C13") (pin "P$1") (pinfunction "P$1_P$1") (pintype "bidirectional"))
      (node (ref "C14") (pin "P$1") (pinfunction "P$1_P$1") (pintype "bidirectional"))
      (node (ref "C15") (pin "P$1") (pinfunction "P$1_P$1") (pintype "bidirectional"))
      (node (ref "C16") (pin "P$1") (pinfunction "P$1_P$1") (pintype "bidirectional"))
      (node (ref "C17") (pin "P$1") (pinfunction "P$1_P$1") (pintype "bidirectional"))
      (node (ref "C18") (pin "P$1") (pinfunction "P$1_P$1") (pintype "bidirectional"))
      (node (ref "C19") (pin "P$1") (pinfunction "P$1_P$1") (pintype "bidirectional"))
      (node (ref "C2") (pin "P$1") (pinfunction "P$1_P$1") (pintype "bidirectional"))
      (node (ref "C20") (pin "P$2") (pinfunction "P$2_P$2") (pintype "bidirectional"))
      (node (ref "C21") (pin "P$2") (pinfunction "P$2_P$2") (pintype "bidirectional"))
      (node (ref "C3") (pin "P$1") (pinfunction "P$1_P$1") (pintype "bidirectional"))
      (node (ref "C4") (pin "P$1") (pinfunction "P$1_P$1") (pintype "bidirectional"))
      (node (ref "C5") (pin "P$1") (pinfunction "P$1_P$1") (pintype "bidirectional"))
      (node (ref "C6") (pin "P$1") (pinfunction "P$1_P$1") (pintype "bidirectional"))
      (node (ref "C7") (pin "P$1") (pinfunction "P$1_P$1") (pintype "bidirectional"))
      (node (ref "C8") (pin "P$1") (pinfunction "P$1_P$1") (pintype "bidirectional"))
      (node (ref "C9") (pin "P$1") (pinfunction "P$1_P$1") (pintype "bidirectional"))
      (node (ref "R3") (pin "P$1") (pinfunction "P$1_P$1") (pintype "bidirectional"))
      (node (ref "R35") (pin "P$2") (pinfunction "P$2_P$2") (pintype "bidirectional"))
      (node (ref "R36") (pin "P$2") (pinfunction "P$2_P$2") (pintype "bidirectional"))
      (node (ref "R37") (pin "P$2") (pinfunction "P$2_P$2") (pintype "bidirectional"))
      (node (ref "R5") (pin "P$1") (pinfunction "P$1_P$1") (pintype "bidirectional"))
      (node (ref "RESET") (pin "4") (pinfunction "4_4") (pintype "passive"))
      (node (ref "SN") (pin "2") (pinfunction "GND_2") (pintype "bidirectional"))
      (node (ref "SN") (pin "8") (pinfunction "RS_8") (pintype "bidirectional"))
      (node (ref "U1") (pin "-I") (pinfunction "GND_IN_-I") (pintype "bidirectional"))
      (node (ref "U1") (pin "-O") (pinfunction "GND_OUT_-O") (pintype "bidirectional"))
      (node (ref "U3") (pin "1") (pinfunction "GND_1") (pintype "bidirectional"))
      (node (ref "U3") (pin "15") (pinfunction "GND_15") (pintype "bidirectional"))
      (node (ref "U3") (pin "38") (pinfunction "GND_38") (pintype "bidirectional"))
      (node (ref "U3") (pin "GND") (pinfunction "GND_GND") (pintype "bidirectional"))
      (node (ref "U4") (pin "1") (pinfunction "GND_1") (pintype "power_in"))
      (node (ref "USB1") (pin "4") (pinfunction "4_4") (pintype "passive"))
      (node (ref "USB1") (pin "SH1") (pinfunction "SHIELD_SH1") (pintype "passive"))
      (node (ref "USB1") (pin "SH2") (pinfunction "SHIELD_SH2") (pintype "passive"))
      (node (ref "USB2") (pin "P$4.GND") (pinfunction "4_P$4.GND") (pintype "passive"))
      (node (ref "USB2") (pin "P$5.SH2") (pinfunction "SHIELD_P$5.SH2") (pintype "passive"))
      (node (ref "USB2") (pin "P$6.SH1") (pinfunction "SHIELD_P$6.SH1") (pintype "passive"))
      (node (ref "VD1") (pin "1") (pinfunction "GND_1") (pintype "bidirectional"))
      (node (ref "VD10") (pin "1") (pinfunction "GND_1") (pintype "bidirectional"))
      (node (ref "VD11") (pin "1") (pinfunction "GND_1") (pintype "bidirectional"))
      (node (ref "VD12") (pin "1") (pinfunction "GND_1") (pintype "bidirectional"))
      (node (ref "VD13") (pin "1") (pinfunction "GND_1") (pintype "bidirectional"))
      (node (ref "VD14") (pin "1") (pinfunction "GND_1") (pintype "bidirectional"))
      (node (ref "VD16") (pin "1") (pinfunction "GND_1") (pintype "bidirectional"))
      (node (ref "VD17") (pin "1") (pinfunction "GND_1") (pintype "bidirectional"))
      (node (ref "VD18") (pin "1") (pinfunction "GND_1") (pintype "bidirectional"))
      (node (ref "VD2") (pin "1") (pinfunction "GND_1") (pintype "bidirectional"))
      (node (ref "VD3") (pin "1") (pinfunction "GND_1") (pintype "bidirectional"))
      (node (ref "VD4") (pin "1") (pinfunction "GND_1") (pintype "bidirectional"))
      (node (ref "VD5") (pin "1") (pinfunction "GND_1") (pintype "bidirectional"))
      (node (ref "VD6") (pin "1") (pinfunction "GND_1") (pintype "bidirectional"))
      (node (ref "VD7") (pin "1") (pinfunction "GND_1") (pintype "bidirectional"))
      (node (ref "VD8") (pin "1") (pinfunction "GND_1") (pintype "bidirectional"))
      (node (ref "VD9") (pin "1") (pinfunction "GND_1") (pintype "bidirectional"))
      (node (ref "X1") (pin "3") (pinfunction "3_3") (pintype "passive"))
      (node (ref "X10") (pin "3") (pinfunction "3_3") (pintype "passive"))
      (node (ref "X11") (pin "3") (pinfunction "3_3") (pintype "passive"))
      (node (ref "X12") (pin "3") (pinfunction "3_3") (pintype "passive"))
      (node (ref "X13") (pin "3") (pinfunction "3_3") (pintype "passive"))
      (node (ref "X14") (pin "3") (pinfunction "3_3") (pintype "passive"))
      (node (ref "X15") (pin "3") (pinfunction "3_3") (pintype "passive"))
      (node (ref "X16") (pin "4") (pinfunction "4_4") (pintype "passive"))
      (node (ref "X17") (pin "5") (pinfunction "5_5") (pintype "passive"))
      (node (ref "X2") (pin "1") (pinfunction "1_1") (pintype "passive"))
      (node (ref "X2") (pin "2") (pinfunction "2_2") (pintype "passive"))
      (node (ref "X3") (pin "3") (pinfunction "3_3") (pintype "passive"))
      (node (ref "X4") (pin "3") (pinfunction "3_3") (pintype "passive"))
      (node (ref "X5") (pin "3") (pinfunction "3_3") (pintype "passive"))
      (node (ref "X6") (pin "3") (pinfunction "3_3") (pintype "passive"))
      (node (ref "X7") (pin "3") (pinfunction "3_3") (pintype "passive"))
      (node (ref "X8") (pin "3") (pinfunction "3_3") (pintype "passive"))
      (node (ref "X9") (pin "3") (pinfunction "3_3") (pintype "passive"))
      (node (ref "ZD1") (pin "A") (pinfunction "A_A") (pintype "passive"))
      (node (ref "ZD10") (pin "A") (pinfunction "A_A") (pintype "passive"))
      (node (ref "ZD11") (pin "A") (pinfunction "A_A") (pintype "passive"))
      (node (ref "ZD12") (pin "A") (pinfunction "A_A") (pintype "passive"))
      (node (ref "ZD13") (pin "A") (pinfunction "A_A") (pintype "passive"))
      (node (ref "ZD14") (pin "A") (pinfunction "A_A") (pintype "passive"))
      (node (ref "ZD15") (pin "A") (pinfunction "A_A") (pintype "passive"))
      (node (ref "ZD16") (pin "A") (pinfunction "A_A") (pintype "passive"))
      (node (ref "ZD17") (pin "A") (pinfunction "A_A") (pintype "passive"))
      (node (ref "ZD18") (pin "A") (pinfunction "A_A") (pintype "passive"))
      (node (ref "ZD2") (pin "A") (pinfunction "A_A") (pintype "passive"))
      (node (ref "ZD3") (pin "A") (pinfunction "A_A") (pintype "passive"))
      (node (ref "ZD4") (pin "A") (pinfunction "A_A") (pintype "passive"))
      (node (ref "ZD5") (pin "A") (pinfunction "A_A") (pintype "passive"))
      (node (ref "ZD6") (pin "A") (pinfunction "A_A") (pintype "passive"))
      (node (ref "ZD7") (pin "A") (pinfunction "A_A") (pintype "passive"))
      (node (ref "ZD8") (pin "A") (pinfunction "A_A") (pintype "passive"))
      (node (ref "ZD9") (pin "A") (pinfunction "A_A") (pintype "passive"))
    )
    (net (code "19") (name "LED_1") (class "Default")
      (node (ref "LED4") (pin "P$2") (pinfunction "A_P$2") (pintype "passive"))
      (node (ref "U3") (pin "13") (pinfunction "IO14_13") (pintype "bidirectional"))
    )
    (net (code "20") (name "LED_2") (class "Default")
      (node (ref "LED5") (pin "P$2") (pinfunction "A_P$2") (pintype "passive"))
      (node (ref "U3") (pin "14") (pinfunction "IO12_14") (pintype "bidirectional"))
    )
    (net (code "21") (name "LED_3") (class "Default")
      (node (ref "LED6") (pin "P$2") (pinfunction "A_P$2") (pintype "passive"))
      (node (ref "U3") (pin "26") (pinfunction "IO4_26") (pintype "bidirectional"))
    )
    (net (code "22") (name "Net-(BOOT-Pad2)") (class "Default")
      (node (ref "BOOT") (pin "2") (pinfunction "2_2") (pintype "passive"))
      (node (ref "C20") (pin "P$1") (pinfunction "P$1_P$1") (pintype "bidirectional"))
      (node (ref "R22") (pin "P$1") (pinfunction "P$1_P$1") (pintype "bidirectional"))
    )
    (net (code "23") (name "Net-(C21-PadP$1)") (class "Default")
      (node (ref "C21") (pin "P$1") (pinfunction "P$1_P$1") (pintype "bidirectional"))
      (node (ref "R23") (pin "P$1") (pinfunction "P$1_P$1") (pintype "bidirectional"))
      (node (ref "RESET") (pin "2") (pinfunction "2_2") (pintype "passive"))
    )
    (net (code "24") (name "Net-(LED1-C)") (class "Default")
      (node (ref "LED1") (pin "P$1") (pinfunction "C_P$1") (pintype "passive"))
      (node (ref "R26") (pin "P$2") (pinfunction "P$2_P$2") (pintype "bidirectional"))
    )
    (net (code "25") (name "Net-(LED2-C)") (class "Default")
      (node (ref "LED2") (pin "P$1") (pinfunction "C_P$1") (pintype "passive"))
      (node (ref "R25") (pin "P$2") (pinfunction "P$2_P$2") (pintype "bidirectional"))
    )
    (net (code "26") (name "Net-(LED4-C)") (class "Default")
      (node (ref "LED4") (pin "P$1") (pinfunction "C_P$1") (pintype "passive"))
      (node (ref "R37") (pin "P$1") (pinfunction "P$1_P$1") (pintype "bidirectional"))
    )
    (net (code "27") (name "Net-(LED5-C)") (class "Default")
      (node (ref "LED5") (pin "P$1") (pinfunction "C_P$1") (pintype "passive"))
      (node (ref "R36") (pin "P$1") (pinfunction "P$1_P$1") (pintype "bidirectional"))
    )
    (net (code "28") (name "Net-(LED6-C)") (class "Default")
      (node (ref "LED6") (pin "P$1") (pinfunction "C_P$1") (pintype "passive"))
      (node (ref "R35") (pin "P$1") (pinfunction "P$1_P$1") (pintype "bidirectional"))
    )
    (net (code "29") (name "Net-(R7-PadP$1)") (class "Default")
      (node (ref "R7") (pin "P$1") (pinfunction "P$1_P$1") (pintype "bidirectional"))
      (node (ref "X1") (pin "2") (pinfunction "2_2") (pintype "passive"))
    )
    (net (code "30") (name "Net-(R8-PadP$1)") (class "Default")
      (node (ref "R8") (pin "P$1") (pinfunction "P$1_P$1") (pintype "bidirectional"))
      (node (ref "X9") (pin "2") (pinfunction "2_2") (pintype "passive"))
    )
    (net (code "31") (name "Net-(R9-PadP$1)") (class "Default")
      (node (ref "R9") (pin "P$1") (pinfunction "P$1_P$1") (pintype "bidirectional"))
      (node (ref "X10") (pin "2") (pinfunction "2_2") (pintype "passive"))
    )
    (net (code "32") (name "Net-(R10-PadP$1)") (class "Default")
      (node (ref "R10") (pin "P$1") (pinfunction "P$1_P$1") (pintype "bidirectional"))
      (node (ref "X3") (pin "2") (pinfunction "2_2") (pintype "passive"))
    )
    (net (code "33") (name "Net-(R11-PadP$1)") (class "Default")
      (node (ref "R11") (pin "P$1") (pinfunction "P$1_P$1") (pintype "bidirectional"))
      (node (ref "X11") (pin "2") (pinfunction "2_2") (pintype "passive"))
    )
    (net (code "34") (name "Net-(R12-PadP$1)") (class "Default")
      (node (ref "R12") (pin "P$1") (pinfunction "P$1_P$1") (pintype "bidirectional"))
      (node (ref "X8") (pin "2") (pinfunction "2_2") (pintype "passive"))
    )
    (net (code "35") (name "Net-(R13-PadP$1)") (class "Default")
      (node (ref "R13") (pin "P$1") (pinfunction "P$1_P$1") (pintype "bidirectional"))
      (node (ref "X12") (pin "2") (pinfunction "2_2") (pintype "passive"))
    )
    (net (code "36") (name "Net-(R14-PadP$1)") (class "Default")
      (node (ref "R14") (pin "P$1") (pinfunction "P$1_P$1") (pintype "bidirectional"))
      (node (ref "X14") (pin "2") (pinfunction "2_2") (pintype "passive"))
    )
    (net (code "37") (name "Net-(R15-PadP$2)") (class "Default")
      (node (ref "R15") (pin "P$2") (pinfunction "P$2_P$2") (pintype "bidirectional"))
      (node (ref "X13") (pin "2") (pinfunction "2_2") (pintype "passive"))
    )
    (net (code "38") (name "Net-(R16-PadP$1)") (class "Default")
      (node (ref "R16") (pin "P$1") (pinfunction "P$1_P$1") (pintype "bidirectional"))
      (node (ref "X4") (pin "2") (pinfunction "2_2") (pintype "passive"))
    )
    (net (code "39") (name "Net-(R27-PadP$1)") (class "Default")
      (node (ref "R27") (pin "P$1") (pinfunction "P$1_P$1") (pintype "bidirectional"))
      (node (ref "R28") (pin "P$2") (pinfunction "P$2_P$2") (pintype "bidirectional"))
      (node (ref "X10") (pin "1") (pinfunction "1_1") (pintype "passive"))
      (node (ref "X11") (pin "1") (pinfunction "1_1") (pintype "passive"))
      (node (ref "X12") (pin "1") (pinfunction "1_1") (pintype "passive"))
      (node (ref "X13") (pin "1") (pinfunction "1_1") (pintype "passive"))
      (node (ref "X14") (pin "1") (pinfunction "1_1") (pintype "passive"))
      (node (ref "X8") (pin "1") (pinfunction "1_1") (pintype "passive"))
      (node (ref "X9") (pin "1") (pinfunction "1_1") (pintype "passive"))
    )
    (net (code "40") (name "Net-(R29-PadP$1)") (class "Default")
      (node (ref "R29") (pin "P$1") (pinfunction "P$1_P$1") (pintype "bidirectional"))
      (node (ref "X7") (pin "2") (pinfunction "2_2") (pintype "passive"))
    )
    (net (code "41") (name "Net-(R30-PadP$1)") (class "Default")
      (node (ref "R30") (pin "P$1") (pinfunction "P$1_P$1") (pintype "bidirectional"))
      (node (ref "X5") (pin "2") (pinfunction "2_2") (pintype "passive"))
    )
    (net (code "42") (name "Net-(R31-PadP$1)") (class "Default")
      (node (ref "R31") (pin "P$1") (pinfunction "P$1_P$1") (pintype "bidirectional"))
      (node (ref "X6") (pin "2") (pinfunction "2_2") (pintype "passive"))
    )
    (net (code "43") (name "Net-(R32-PadP$1)") (class "Default")
      (node (ref "R32") (pin "P$1") (pinfunction "P$1_P$1") (pintype "bidirectional"))
      (node (ref "X15") (pin "2") (pinfunction "2_2") (pintype "passive"))
    )
    (net (code "44") (name "Net-(R33-PadP$2)") (class "Default")
      (node (ref "R33") (pin "P$2") (pinfunction "P$2_P$2") (pintype "bidirectional"))
      (node (ref "VD15") (pin "A") (pinfunction "A_A") (pintype "passive"))
    )
    (net (code "45") (name "Net-(SN-VCC)") (class "Default")
      (node (ref "R18") (pin "P$2") (pinfunction "P$2_P$2") (pintype "bidirectional"))
      (node (ref "SN") (pin "3") (pinfunction "VCC_3") (pintype "bidirectional"))
    )
    (net (code "46") (name "Net-(U1-+V_OUT)") (class "Default")
      (node (ref "C5") (pin "P$2") (pinfunction "P$2_P$2") (pintype "bidirectional"))
      (node (ref "C6") (pin "P$2") (pinfunction "P$2_P$2") (pintype "bidirectional"))
      (node (ref "L1") (pin "1") (pinfunction "1_1") (pintype "passive"))
      (node (ref "U1") (pin "+O") (pinfunction "+V_OUT_+O") (pintype "bidirectional"))
    )
    (net (code "47") (name "Net-(U2-ADJ{slash}GND)") (class "Default")
      (node (ref "R4") (pin "P$1") (pinfunction "P$1_P$1") (pintype "bidirectional"))
      (node (ref "R5") (pin "P$2") (pinfunction "P$2_P$2") (pintype "bidirectional"))
      (node (ref "U2") (pin "1") (pinfunction "ADJ/GND_1") (pintype "input"))
    )
    (net (code "48") (name "Net-(U3-3V3)") (class "Default")
      (node (ref "R6") (pin "P$1") (pinfunction "P$1_P$1") (pintype "bidirectional"))
      (node (ref "U3") (pin "2") (pinfunction "3V3_2") (pintype "bidirectional"))
    )
    (net (code "49") (name "Net-(U4-DTR)") (class "Default")
      (node (ref "R20") (pin "P$1") (pinfunction "P$1_P$1") (pintype "bidirectional"))
      (node (ref "U4") (pin "13") (pinfunction "DTR_13") (pintype "bidirectional"))
      (node (ref "VT1") (pin "2") (pinfunction "E_2") (pintype "passive"))
    )
    (net (code "50") (name "Net-(U4-RTS)") (class "Default")
      (node (ref "R19") (pin "P$1") (pinfunction "P$1_P$1") (pintype "bidirectional"))
      (node (ref "U4") (pin "14") (pinfunction "RTS_14") (pintype "bidirectional"))
      (node (ref "VT2") (pin "2") (pinfunction "E_2") (pintype "passive"))
    )
    (net (code "51") (name "Net-(U4-V3)") (class "Default")
      (node (ref "C14") (pin "P$2") (pinfunction "P$2_P$2") (pintype "bidirectional"))
      (node (ref "C18") (pin "P$2") (pinfunction "P$2_P$2") (pintype "bidirectional"))
      (node (ref "C19") (pin "P$2") (pinfunction "P$2_P$2") (pintype "bidirectional"))
      (node (ref "R21") (pin "P$1") (pinfunction "P$1_P$1") (pintype "bidirectional"))
      (node (ref "U4") (pin "16") (pinfunction "VCC_16") (pintype "power_in"))
      (node (ref "U4") (pin "4") (pinfunction "V3_4") (pintype "power_in"))
    )
    (net (code "52") (name "Net-(U4-XI)") (class "Default")
      (node (ref "C15") (pin "P$2") (pinfunction "P$2_P$2") (pintype "bidirectional"))
      (node (ref "U4") (pin "7") (pinfunction "XI_7") (pintype "input"))
      (node (ref "Z1") (pin "1") (pinfunction "1_1") (pintype "passive"))
    )
    (net (code "53") (name "Net-(U4-XO)") (class "Default")
      (node (ref "C16") (pin "P$2") (pinfunction "P$2_P$2") (pintype "bidirectional"))
      (node (ref "U4") (pin "8") (pinfunction "XO_8") (pintype "output"))
      (node (ref "Z1") (pin "3") (pinfunction "2_3") (pintype "passive"))
    )
    (net (code "54") (name "Net-(USB1-Pad2)") (class "Default")
      (node (ref "USB1") (pin "2") (pinfunction "2_2") (pintype "passive"))
      (node (ref "USB1") (pin "3") (pinfunction "3_3") (pintype "passive"))
    )
    (net (code "55") (name "Net-(USB2-1)") (class "Default")
      (node (ref "R33") (pin "P$1") (pinfunction "P$1_P$1") (pintype "bidirectional"))
      (node (ref "USB2") (pin "P$1.5V") (pinfunction "1_P$1.5V") (pintype "passive"))
    )
    (net (code "56") (name "Net-(VT1-B)") (class "Default")
      (node (ref "R19") (pin "P$2") (pinfunction "P$2_P$2") (pintype "bidirectional"))
      (node (ref "VT1") (pin "1") (pinfunction "B_1") (pintype "passive"))
    )
    (net (code "57") (name "Net-(VT1-C)") (class "Default")
      (node (ref "R39") (pin "P$2") (pinfunction "P$2_P$2") (pintype "bidirectional"))
      (node (ref "VT1") (pin "3") (pinfunction "C_3") (pintype "passive"))
    )
    (net (code "58") (name "Net-(VT2-B)") (class "Default")
      (node (ref "R20") (pin "P$2") (pinfunction "P$2_P$2") (pintype "bidirectional"))
      (node (ref "VT2") (pin "1") (pinfunction "B_1") (pintype "passive"))
    )
    (net (code "59") (name "Net-(VT2-C)") (class "Default")
      (node (ref "R38") (pin "P$1") (pinfunction "P$1_P$1") (pintype "bidirectional"))
      (node (ref "VT2") (pin "3") (pinfunction "C_3") (pintype "passive"))
    )
    (net (code "60") (name "RESET") (class "Default")
      (node (ref "C17") (pin "P$2") (pinfunction "P$2_P$2") (pintype "bidirectional"))
      (node (ref "R23") (pin "P$2") (pinfunction "P$2_P$2") (pintype "bidirectional"))
      (node (ref "R24") (pin "P$2") (pinfunction "P$2_P$2") (pintype "bidirectional"))
      (node (ref "R38") (pin "P$2") (pinfunction "P$2_P$2") (pintype "bidirectional"))
      (node (ref "U3") (pin "3") (pinfunction "EN_3") (pintype "bidirectional"))
    )
    (net (code "61") (name "RX") (class "Default")
      (node (ref "R26") (pin "P$1") (pinfunction "P$1_P$1") (pintype "bidirectional"))
      (node (ref "U3") (pin "35") (pinfunction "TXD0_35") (pintype "bidirectional"))
      (node (ref "U4") (pin "3") (pinfunction "RX_3") (pintype "input"))
    )
    (net (code "62") (name "SERV1_IN") (class "Default")
      (node (ref "R7") (pin "P$2") (pinfunction "P$2_P$2") (pintype "bidirectional"))
      (node (ref "U3") (pin "12") (pinfunction "IO27_12") (pintype "bidirectional"))
      (node (ref "VD11") (pin "3") (pinfunction "I/O_3") (pintype "bidirectional"))
      (node (ref "ZD5") (pin "C") (pinfunction "C_C") (pintype "passive"))
    )
    (net (code "63") (name "SERV2_IN") (class "Default")
      (node (ref "R10") (pin "P$2") (pinfunction "P$2_P$2") (pintype "bidirectional"))
      (node (ref "U3") (pin "16") (pinfunction "IO13_16") (pintype "bidirectional"))
      (node (ref "VD12") (pin "3") (pinfunction "I/O_3") (pintype "bidirectional"))
      (node (ref "ZD4") (pin "C") (pinfunction "C_C") (pintype "passive"))
    )
    (net (code "64") (name "SERV3_IN") (class "Default")
      (node (ref "R16") (pin "P$2") (pinfunction "P$2_P$2") (pintype "bidirectional"))
      (node (ref "U3") (pin "27") (pinfunction "IO16_27") (pintype "bidirectional"))
      (node (ref "VD3") (pin "3") (pinfunction "I/O_3") (pintype "bidirectional"))
      (node (ref "ZD12") (pin "C") (pinfunction "C_C") (pintype "passive"))
    )
    (net (code "65") (name "SERV4_IN") (class "Default")
      (node (ref "R30") (pin "P$2") (pinfunction "P$2_P$2") (pintype "bidirectional"))
      (node (ref "U3") (pin "28") (pinfunction "IO17_28") (pintype "bidirectional"))
      (node (ref "VD4") (pin "3") (pinfunction "I/O_3") (pintype "bidirectional"))
      (node (ref "ZD13") (pin "C") (pinfunction "C_C") (pintype "passive"))
    )
    (net (code "66") (name "SERV5_IN") (class "Default")
      (node (ref "R31") (pin "P$2") (pinfunction "P$2_P$2") (pintype "bidirectional"))
      (node (ref "U3") (pin "30") (pinfunction "IO18_30") (pintype "bidirectional"))
      (node (ref "VD5") (pin "3") (pinfunction "I/O_3") (pintype "bidirectional"))
      (node (ref "ZD14") (pin "C") (pinfunction "C_C") (pintype "passive"))
    )
    (net (code "67") (name "SERV6_IN") (class "Default")
      (node (ref "R29") (pin "P$2") (pinfunction "P$2_P$2") (pintype "bidirectional"))
      (node (ref "U3") (pin "33") (pinfunction "IO21_33") (pintype "bidirectional"))
      (node (ref "VD14") (pin "3") (pinfunction "I/O_3") (pintype "bidirectional"))
      (node (ref "ZD15") (pin "C") (pinfunction "C_C") (pintype "passive"))
    )
    (net (code "68") (name "SERV7_IN") (class "Default")
      (node (ref "R32") (pin "P$2") (pinfunction "P$2_P$2") (pintype "bidirectional"))
      (node (ref "U3") (pin "36") (pinfunction "IO22_36") (pintype "bidirectional"))
      (node (ref "VD8") (pin "3") (pinfunction "I/O_3") (pintype "bidirectional"))
      (node (ref "ZD17") (pin "C") (pinfunction "C_C") (pintype "passive"))
    )
    (net (code "69") (name "TX") (class "Default")
      (node (ref "R25") (pin "P$1") (pinfunction "P$1_P$1") (pintype "bidirectional"))
      (node (ref "U3") (pin "34") (pinfunction "RXD0_34") (pintype "bidirectional"))
      (node (ref "U4") (pin "2") (pinfunction "TX_2") (pintype "output"))
    )
    (net (code "70") (name "U_ACUM") (class "Default")
      (node (ref "R2") (pin "P$1") (pinfunction "P$1_P$1") (pintype "bidirectional"))
      (node (ref "R3") (pin "P$2") (pinfunction "P$2_P$2") (pintype "bidirectional"))
      (node (ref "U3") (pin "7") (pinfunction "IO35_7") (pintype "input"))
      (node (ref "VD16") (pin "3") (pinfunction "I/O_3") (pintype "bidirectional"))
      (node (ref "ZD18") (pin "C") (pinfunction "C_C") (pintype "passive"))
    )
    (net (code "71") (name "VIN") (class "Default")
      (node (ref "R1") (pin "1") (pinfunction "P$1_1") (pintype "bidirectional"))
      (node (ref "X2") (pin "3") (pinfunction "3_3") (pintype "passive"))
      (node (ref "X2") (pin "4") (pinfunction "4_4") (pintype "passive"))
    )
    (net (code "72") (name "unconnected-(BOOT-Pad1)") (class "Default")
      (node (ref "BOOT") (pin "1") (pinfunction "1_1") (pintype "passive"))
    )
    (net (code "73") (name "unconnected-(BOOT-Pad3)") (class "Default")
      (node (ref "BOOT") (pin "3") (pinfunction "3_3") (pintype "passive"))
    )
    (net (code "74") (name "unconnected-(RESET-Pad1)") (class "Default")
      (node (ref "RESET") (pin "1") (pinfunction "1_1") (pintype "passive"))
    )
    (net (code "75") (name "unconnected-(RESET-Pad3)") (class "Default")
      (node (ref "RESET") (pin "3") (pinfunction "3_3") (pintype "passive"))
    )
    (net (code "76") (name "unconnected-(SN-LBK-Pad5)") (class "Default")
      (node (ref "SN") (pin "5") (pinfunction "LBK_5") (pintype "bidirectional"))
    )
    (net (code "77") (name "unconnected-(U3-CLK-Pad20)") (class "Default")
      (node (ref "U3") (pin "20") (pinfunction "CLK_20") (pintype "bidirectional"))
    )
    (net (code "78") (name "unconnected-(U3-CMD-Pad19)") (class "Default")
      (node (ref "U3") (pin "19") (pinfunction "CMD_19") (pintype "bidirectional"))
    )
    (net (code "79") (name "unconnected-(U3-IO2-Pad24)") (class "Default")
      (node (ref "U3") (pin "24") (pinfunction "IO2_24") (pintype "bidirectional"))
    )
    (net (code "80") (name "unconnected-(U3-IO5-Pad29)") (class "Default")
      (node (ref "U3") (pin "29") (pinfunction "IO5_29") (pintype "bidirectional"))
    )
    (net (code "81") (name "unconnected-(U3-IO15-Pad23)") (class "Default")
      (node (ref "U3") (pin "23") (pinfunction "IO15_23") (pintype "bidirectional"))
    )
    (net (code "82") (name "unconnected-(U3-NC-Pad32)") (class "Default")
      (node (ref "U3") (pin "32") (pinfunction "NC_32") (pintype "bidirectional"))
    )
    (net (code "83") (name "unconnected-(U3-SD1-Pad22)") (class "Default")
      (node (ref "U3") (pin "22") (pinfunction "SD1_22") (pintype "bidirectional"))
    )
    (net (code "84") (name "unconnected-(U3-SD2-Pad17)") (class "Default")
      (node (ref "U3") (pin "17") (pinfunction "SD2_17") (pintype "bidirectional"))
    )
    (net (code "85") (name "unconnected-(U3-SD3-Pad18)") (class "Default")
      (node (ref "U3") (pin "18") (pinfunction "SD3_18") (pintype "bidirectional"))
    )
    (net (code "86") (name "unconnected-(U3-SDO-Pad21)") (class "Default")
      (node (ref "U3") (pin "21") (pinfunction "SDO_21") (pintype "bidirectional"))
    )
    (net (code "87") (name "unconnected-(U4-CTS-Pad9)") (class "Default")
      (node (ref "U4") (pin "9") (pinfunction "CTS_9") (pintype "bidirectional"))
    )
    (net (code "88") (name "unconnected-(U4-DCD-Pad12)") (class "Default")
      (node (ref "U4") (pin "12") (pinfunction "DCD_12") (pintype "bidirectional"))
    )
    (net (code "89") (name "unconnected-(U4-DSR-Pad10)") (class "Default")
      (node (ref "U4") (pin "10") (pinfunction "DSR_10") (pintype "bidirectional"))
    )
    (net (code "90") (name "unconnected-(U4-R232-Pad15)") (class "Default")
      (node (ref "U4") (pin "15") (pinfunction "R232_15") (pintype "bidirectional"))
    )
    (net (code "91") (name "unconnected-(U4-RI-Pad11)") (class "Default")
      (node (ref "U4") (pin "11") (pinfunction "RI_11") (pintype "bidirectional"))
    )
  )
)
